# Clock.net
KiCad netlist of a schematic drawn in EAGLE
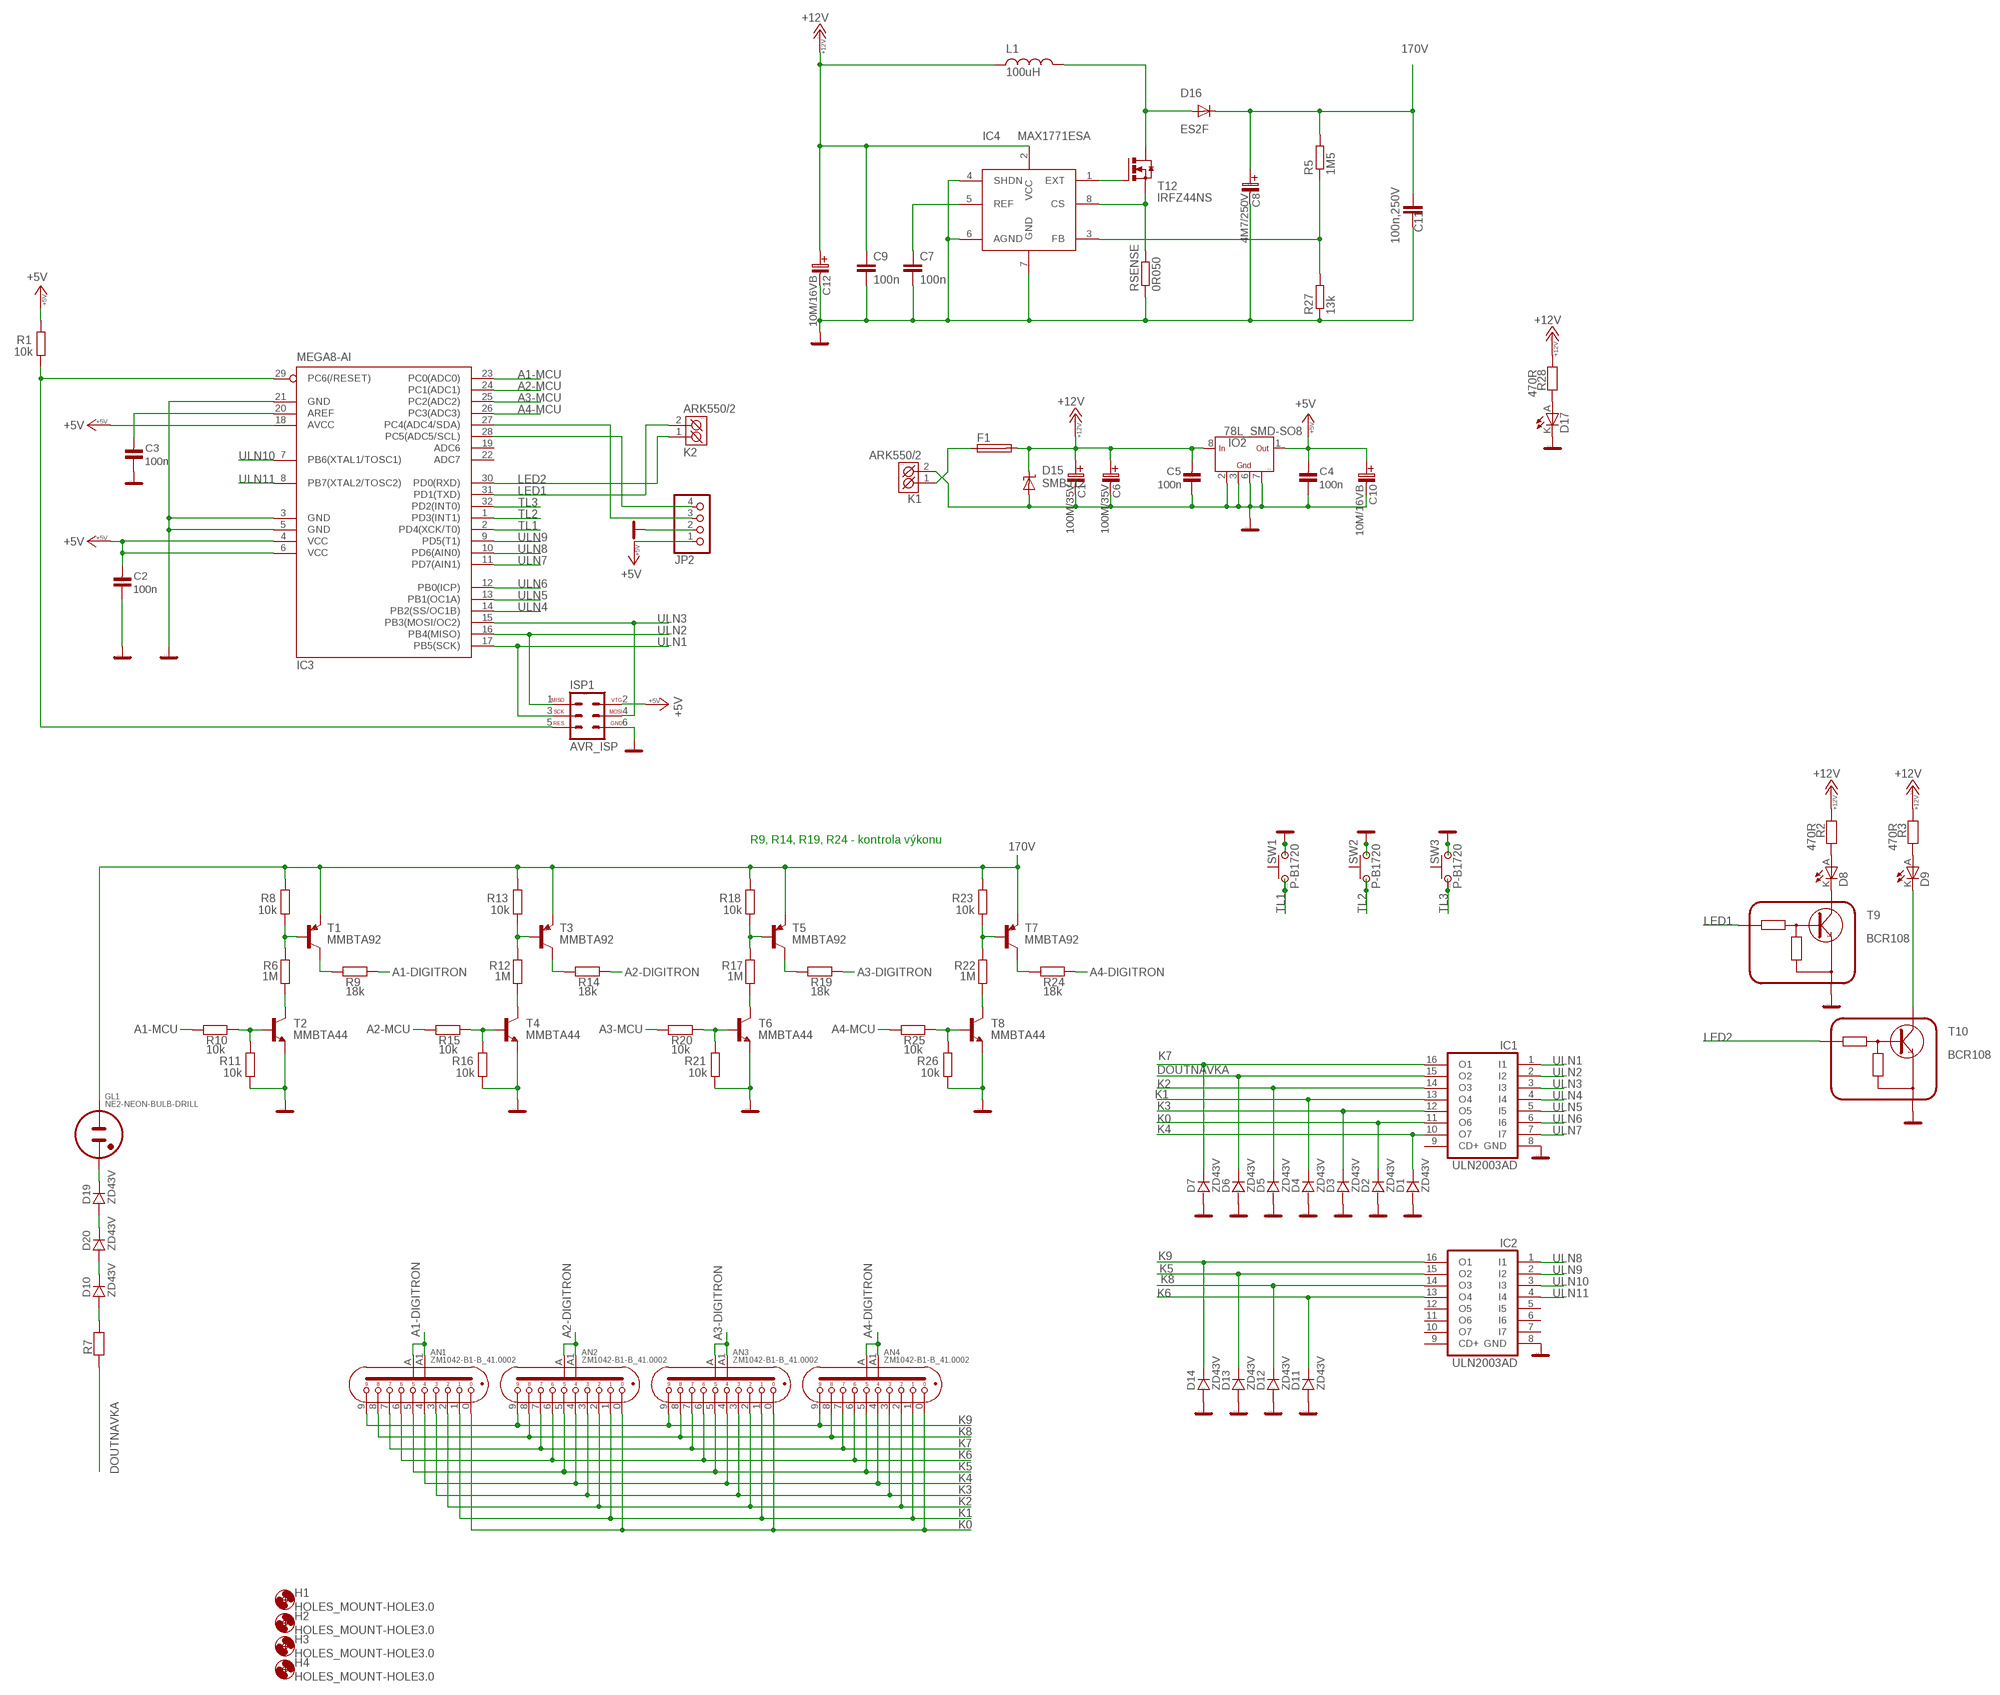
[diagram p0: schematic, sheet 1]

(export (version "E")
  (design (tool "Eeschema 10.0.6"))
  (components
    (comp (ref "AN1")
      (value "ZM1042-B1-B_41.0002")
      (footprint "eagle-import:ZM1042-MULTI-CONTACT")
      (libsource (lib "eagle-import") (part "ZM1042-B1-B_41.0002"))
    )
    (comp (ref "AN2")
      (value "ZM1042-B1-B_41.0002")
      (footprint "eagle-import:ZM1042-MULTI-CONTACT")
      (libsource (lib "eagle-import") (part "ZM1042-B1-B_41.0002"))
    )
    (comp (ref "AN3")
      (value "ZM1042-B1-B_41.0002")
      (footprint "eagle-import:ZM1042-MULTI-CONTACT")
      (libsource (lib "eagle-import") (part "ZM1042-B1-B_41.0002"))
    )
    (comp (ref "AN4")
      (value "ZM1042-B1-B_41.0002")
      (footprint "eagle-import:ZM1042-MULTI-CONTACT")
      (libsource (lib "eagle-import") (part "ZM1042-B1-B_41.0002"))
    )
    (comp (ref "C1")
      (value "100M/35V")
      (footprint "eagle-import:C_EL_3,5")
      (libsource (lib "eagle-import") (part "100M/35V"))
    )
    (comp (ref "C2")
      (value "100n")
      (footprint "eagle-import:0805")
      (libsource (lib "eagle-import") (part "C-KERAMIK_SMD_0805"))
    )
    (comp (ref "C3")
      (value "100n")
      (footprint "eagle-import:0805")
      (libsource (lib "eagle-import") (part "C-KERAMIK_SMD_0805"))
    )
    (comp (ref "C4")
      (value "100n")
      (footprint "eagle-import:0805")
      (libsource (lib "eagle-import") (part "C-KERAMIK_SMD_0805"))
    )
    (comp (ref "C5")
      (value "100n")
      (footprint "eagle-import:0805")
      (libsource (lib "eagle-import") (part "C-KERAMIK_SMD_0805"))
    )
    (comp (ref "C6")
      (value "100M/35V")
      (footprint "eagle-import:C_EL_3,5")
      (libsource (lib "eagle-import") (part "100M/35V"))
    )
    (comp (ref "C7")
      (value "100n")
      (footprint "eagle-import:C0805")
      (libsource (lib "eagle-import") (part "C-EUC0805"))
    )
    (comp (ref "C8")
      (value "4M7/250V")
      (footprint "eagle-import:C_EL_3,5")
      (libsource (lib "eagle-import") (part "4M7/250V"))
    )
    (comp (ref "C9")
      (value "100n")
      (footprint "eagle-import:C0805")
      (libsource (lib "eagle-import") (part "C-EUC0805"))
    )
    (comp (ref "C10")
      (value "10M/16VB")
      (footprint "eagle-import:B")
      (libsource (lib "eagle-import") (part "10M/16VB"))
    )
    (comp (ref "C11")
      (value "100n,250V")
      (footprint "eagle-import:C2420")
      (libsource (lib "eagle-import") (part "C-EU-2420"))
    )
    (comp (ref "C12")
      (value "10M/16VB")
      (footprint "eagle-import:B")
      (libsource (lib "eagle-import") (part "10M/16VB"))
    )
    (comp (ref "D1")
      (value "ZD43V")
      (footprint "eagle-import:SOD-80")
      (libsource (lib "eagle-import") (part "1N4148_SOD80"))
    )
    (comp (ref "D2")
      (value "ZD43V")
      (footprint "eagle-import:SOD-80")
      (libsource (lib "eagle-import") (part "1N4148_SOD80"))
    )
    (comp (ref "D3")
      (value "ZD43V")
      (footprint "eagle-import:SOD-80")
      (libsource (lib "eagle-import") (part "1N4148_SOD80"))
    )
    (comp (ref "D4")
      (value "ZD43V")
      (footprint "eagle-import:SOD-80")
      (libsource (lib "eagle-import") (part "1N4148_SOD80"))
    )
    (comp (ref "D5")
      (value "ZD43V")
      (footprint "eagle-import:SOD-80")
      (libsource (lib "eagle-import") (part "1N4148_SOD80"))
    )
    (comp (ref "D6")
      (value "ZD43V")
      (footprint "eagle-import:SOD-80")
      (libsource (lib "eagle-import") (part "1N4148_SOD80"))
    )
    (comp (ref "D7")
      (value "ZD43V")
      (footprint "eagle-import:SOD-80")
      (libsource (lib "eagle-import") (part "1N4148_SOD80"))
    )
    (comp (ref "D8")
      (value "LEDLED3MM")
      (footprint "eagle-import:LED3MM")
      (libsource (lib "eagle-import") (part "LEDLED3MM"))
    )
    (comp (ref "D9")
      (value "LEDLED3MM")
      (footprint "eagle-import:LED3MM")
      (libsource (lib "eagle-import") (part "LEDLED3MM"))
    )
    (comp (ref "D10")
      (value "ZD43V")
      (footprint "eagle-import:SOD-80")
      (libsource (lib "eagle-import") (part "1N4148_SOD80"))
    )
    (comp (ref "D11")
      (value "ZD43V")
      (footprint "eagle-import:SOD-80")
      (libsource (lib "eagle-import") (part "1N4148_SOD80"))
    )
    (comp (ref "D12")
      (value "ZD43V")
      (footprint "eagle-import:SOD-80")
      (libsource (lib "eagle-import") (part "1N4148_SOD80"))
    )
    (comp (ref "D13")
      (value "ZD43V")
      (footprint "eagle-import:SOD-80")
      (libsource (lib "eagle-import") (part "1N4148_SOD80"))
    )
    (comp (ref "D14")
      (value "ZD43V")
      (footprint "eagle-import:SOD-80")
      (libsource (lib "eagle-import") (part "1N4148_SOD80"))
    )
    (comp (ref "D15")
      (value "SMBJ12")
      (footprint "eagle-import:SMBJ")
      (libsource (lib "eagle-import") (part "SUPPRESSOR-SMBJ"))
    )
    (comp (ref "D16")
      (value "ES2F")
      (footprint "eagle-import:SMC")
      (libsource (lib "eagle-import") (part "DIODE-SMC"))
    )
    (comp (ref "D17")
      (value "LEDLED3MM")
      (footprint "eagle-import:LED3MM")
      (libsource (lib "eagle-import") (part "LEDLED3MM"))
    )
    (comp (ref "D19")
      (value "ZD43V")
      (footprint "eagle-import:SOD-80")
      (libsource (lib "eagle-import") (part "1N4148_SOD80"))
    )
    (comp (ref "D20")
      (value "ZD43V")
      (footprint "eagle-import:SOD-80")
      (libsource (lib "eagle-import") (part "1N4148_SOD80"))
    )
    (comp (ref "F1")
      (value "TE5")
      (footprint "eagle-import:TE5")
      (libsource (lib "eagle-import") (part "TE5"))
    )
    (comp (ref "GL1")
      (value "NE2-NEON-BULB-DRILL")
      (footprint "eagle-import:NE2-NEON-BULB-DRILL")
      (libsource (lib "eagle-import") (part "NE2-NEON-BULB-DRILL"))
    )
    (comp (ref "H1")
      (value "HOLES_MOUNT-HOLE3.0")
      (footprint "eagle-import:HOLES_3,0")
      (libsource (lib "eagle-import") (part "HOLES_MOUNT-HOLE3.0"))
    )
    (comp (ref "H2")
      (value "HOLES_MOUNT-HOLE3.0")
      (footprint "eagle-import:HOLES_3,0")
      (libsource (lib "eagle-import") (part "HOLES_MOUNT-HOLE3.0"))
    )
    (comp (ref "H3")
      (value "HOLES_MOUNT-HOLE3.0")
      (footprint "eagle-import:HOLES_3,0")
      (libsource (lib "eagle-import") (part "HOLES_MOUNT-HOLE3.0"))
    )
    (comp (ref "H4")
      (value "HOLES_MOUNT-HOLE3.0")
      (footprint "eagle-import:HOLES_3,0")
      (libsource (lib "eagle-import") (part "HOLES_MOUNT-HOLE3.0"))
    )
    (comp (ref "IC1")
      (value "ULN2003AD")
      (footprint "eagle-import:SO16")
      (libsource (lib "eagle-import") (part "ULN2003AD"))
    )
    (comp (ref "IC2")
      (value "ULN2003AD")
      (footprint "eagle-import:SO16")
      (libsource (lib "eagle-import") (part "ULN2003AD"))
    )
    (comp (ref "IC3")
      (value "MEGA8-AI")
      (footprint "eagle-import:TQFP32-08")
      (fields (field (name "MPN") "ATMEGA8-16AU"))
      (libsource (lib "eagle-import") (part "MEGA8-AI"))
    )
    (comp (ref "IC4")
      (value "MAX1771ESA")
      (footprint "eagle-import:SO-8")
      (libsource (lib "eagle-import") (part "MAX1771ESA"))
    )
    (comp (ref "IO2")
      (value "78L_SMD-SO8")
      (footprint "eagle-import:SO08")
      (libsource (lib "eagle-import") (part "78L??_SMD-SO8"))
    )
    (comp (ref "ISP1")
      (value "AVR_ISP")
      (footprint "eagle-import:MLW06G")
      (libsource (lib "eagle-import") (part "AVR_ISP"))
    )
    (comp (ref "JP2")
      (value "PINHD-1X4")
      (footprint "eagle-import:1X04")
      (libsource (lib "eagle-import") (part "PINHD-1X4"))
    )
    (comp (ref "K1")
      (value "ARK550/2")
      (footprint "eagle-import:ARK550_2")
      (libsource (lib "eagle-import") (part "ARK550/2"))
    )
    (comp (ref "K2")
      (value "ARK550/2")
      (footprint "eagle-import:ARK550_2")
      (libsource (lib "eagle-import") (part "ARK550/2"))
    )
    (comp (ref "L1")
      (value "100uH")
      (footprint "eagle-import:L-B82479")
      (libsource (lib "eagle-import") (part "L-SMT-POWER-B82479"))
    )
    (comp (ref "R1")
      (value "10k")
      (footprint "eagle-import:0805")
      (libsource (lib "eagle-import") (part "R_SMD_0805"))
    )
    (comp (ref "R2")
      (value "470R")
      (footprint "eagle-import:0805")
      (libsource (lib "eagle-import") (part "#PaJa_30_R_SMD_0805"))
    )
    (comp (ref "R3")
      (value "470R")
      (footprint "eagle-import:0805")
      (libsource (lib "eagle-import") (part "#PaJa_30_R_SMD_0805"))
    )
    (comp (ref "R5")
      (value "1M5")
      (footprint "eagle-import:R0805")
      (libsource (lib "eagle-import") (part "R-EU_R0805"))
    )
    (comp (ref "R6")
      (value "1M")
      (footprint "eagle-import:0805")
      (libsource (lib "eagle-import") (part "R_SMD_0805"))
    )
    (comp (ref "R7")
      (value "W2_180K")
      (footprint "eagle-import:R__2W")
      (libsource (lib "eagle-import") (part "W2_180K"))
    )
    (comp (ref "R8")
      (value "10k")
      (footprint "eagle-import:0805")
      (libsource (lib "eagle-import") (part "R_SMD_0805"))
    )
    (comp (ref "R9")
      (value "18k")
      (footprint "eagle-import:1206")
      (libsource (lib "eagle-import") (part "#PaJa_30_R_SMD_1206"))
    )
    (comp (ref "R10")
      (value "10k")
      (footprint "eagle-import:0805")
      (libsource (lib "eagle-import") (part "#PaJa_30_R_SMD_0805"))
    )
    (comp (ref "R11")
      (value "10k")
      (footprint "eagle-import:0805")
      (libsource (lib "eagle-import") (part "R_SMD_0805"))
    )
    (comp (ref "R12")
      (value "1M")
      (footprint "eagle-import:0805")
      (libsource (lib "eagle-import") (part "R_SMD_0805"))
    )
    (comp (ref "R13")
      (value "10k")
      (footprint "eagle-import:0805")
      (libsource (lib "eagle-import") (part "R_SMD_0805"))
    )
    (comp (ref "R14")
      (value "18k")
      (footprint "eagle-import:1206")
      (libsource (lib "eagle-import") (part "#PaJa_30_R_SMD_1206"))
    )
    (comp (ref "R15")
      (value "10k")
      (footprint "eagle-import:0805")
      (libsource (lib "eagle-import") (part "#PaJa_30_R_SMD_0805"))
    )
    (comp (ref "R16")
      (value "10k")
      (footprint "eagle-import:0805")
      (libsource (lib "eagle-import") (part "R_SMD_0805"))
    )
    (comp (ref "R17")
      (value "1M")
      (footprint "eagle-import:0805")
      (libsource (lib "eagle-import") (part "R_SMD_0805"))
    )
    (comp (ref "R18")
      (value "10k")
      (footprint "eagle-import:0805")
      (libsource (lib "eagle-import") (part "R_SMD_0805"))
    )
    (comp (ref "R19")
      (value "18k")
      (footprint "eagle-import:1206")
      (libsource (lib "eagle-import") (part "#PaJa_30_R_SMD_1206"))
    )
    (comp (ref "R20")
      (value "10k")
      (footprint "eagle-import:0805")
      (libsource (lib "eagle-import") (part "#PaJa_30_R_SMD_0805"))
    )
    (comp (ref "R21")
      (value "10k")
      (footprint "eagle-import:0805")
      (libsource (lib "eagle-import") (part "R_SMD_0805"))
    )
    (comp (ref "R22")
      (value "1M")
      (footprint "eagle-import:0805")
      (libsource (lib "eagle-import") (part "R_SMD_0805"))
    )
    (comp (ref "R23")
      (value "10k")
      (footprint "eagle-import:0805")
      (libsource (lib "eagle-import") (part "R_SMD_0805"))
    )
    (comp (ref "R24")
      (value "18k")
      (footprint "eagle-import:1206")
      (libsource (lib "eagle-import") (part "#PaJa_30_R_SMD_1206"))
    )
    (comp (ref "R25")
      (value "10k")
      (footprint "eagle-import:0805")
      (libsource (lib "eagle-import") (part "#PaJa_30_R_SMD_0805"))
    )
    (comp (ref "R26")
      (value "10k")
      (footprint "eagle-import:0805")
      (libsource (lib "eagle-import") (part "R_SMD_0805"))
    )
    (comp (ref "R27")
      (value "13k")
      (footprint "eagle-import:R0805")
      (libsource (lib "eagle-import") (part "R-EU_R0805"))
    )
    (comp (ref "R28")
      (value "470R")
      (footprint "eagle-import:0805")
      (libsource (lib "eagle-import") (part "#PaJa_30_R_SMD_0805"))
    )
    (comp (ref "RSENSE")
      (value "0R050")
      (footprint "eagle-import:R2010")
      (libsource (lib "eagle-import") (part "R-EU_R2010"))
    )
    (comp (ref "SW1")
      (value "P-B1720")
      (footprint "eagle-import:P-B1720")
      (libsource (lib "eagle-import") (part "P-B1720"))
    )
    (comp (ref "SW2")
      (value "P-B1720")
      (footprint "eagle-import:P-B1720")
      (libsource (lib "eagle-import") (part "P-B1720"))
    )
    (comp (ref "SW3")
      (value "P-B1720")
      (footprint "eagle-import:P-B1720")
      (libsource (lib "eagle-import") (part "P-B1720"))
    )
    (comp (ref "T1")
      (value "MMBTA92")
      (footprint "eagle-import:SOT23-BEC")
      (libsource (lib "eagle-import") (part "-PNP-SOT23-BECMMBTA92LT1"))
    )
    (comp (ref "T2")
      (value "MMBTA44")
      (footprint "eagle-import:SOT23-BEC")
      (libsource (lib "eagle-import") (part "-NPN-SOT23-BECMMBTA42LT1"))
    )
    (comp (ref "T3")
      (value "MMBTA92")
      (footprint "eagle-import:SOT23-BEC")
      (libsource (lib "eagle-import") (part "-PNP-SOT23-BECMMBTA92LT1"))
    )
    (comp (ref "T4")
      (value "MMBTA44")
      (footprint "eagle-import:SOT23-BEC")
      (libsource (lib "eagle-import") (part "-NPN-SOT23-BECMMBTA42LT1"))
    )
    (comp (ref "T5")
      (value "MMBTA92")
      (footprint "eagle-import:SOT23-BEC")
      (libsource (lib "eagle-import") (part "-PNP-SOT23-BECMMBTA92LT1"))
    )
    (comp (ref "T6")
      (value "MMBTA44")
      (footprint "eagle-import:SOT23-BEC")
      (libsource (lib "eagle-import") (part "-NPN-SOT23-BECMMBTA42LT1"))
    )
    (comp (ref "T7")
      (value "MMBTA92")
      (footprint "eagle-import:SOT23-BEC")
      (libsource (lib "eagle-import") (part "-PNP-SOT23-BECMMBTA92LT1"))
    )
    (comp (ref "T8")
      (value "MMBTA44")
      (footprint "eagle-import:SOT23-BEC")
      (libsource (lib "eagle-import") (part "-NPN-SOT23-BECMMBTA42LT1"))
    )
    (comp (ref "T9")
      (value "BCR108")
      (footprint "eagle-import:SOT-23")
      (libsource (lib "eagle-import") (part "BCR108"))
    )
    (comp (ref "T10")
      (value "BCR108")
      (footprint "eagle-import:SOT-23")
      (libsource (lib "eagle-import") (part "BCR108"))
    )
    (comp (ref "T12")
      (value "IRFZ44NS")
      (footprint "eagle-import:D2PACK")
      (libsource (lib "eagle-import") (part "IRF3704S"))
    )
  )
  (nets
    (net (code "1") (name "+5V") (class "Default")
      (node (ref "C10") (pin "+") (pinfunction "C_EL+_+") (pintype "passive"))
      (node (ref "C2") (pin "2") (pinfunction "2_2") (pintype "passive"))
      (node (ref "C4") (pin "2") (pinfunction "2_2") (pintype "passive"))
      (node (ref "IC3") (pin "18") (pinfunction "AVCC_18") (pintype "power_in"))
      (node (ref "IC3") (pin "4") (pinfunction "VCC_4") (pintype "power_in"))
      (node (ref "IC3") (pin "6") (pinfunction "VCC_6") (pintype "power_in"))
      (node (ref "IO2") (pin "1") (pinfunction "OUT_1") (pintype "output"))
      (node (ref "ISP1") (pin "2") (pinfunction "2_2") (pintype "passive"))
      (node (ref "JP2") (pin "1") (pinfunction "1_1") (pintype "passive"))
      (node (ref "R1") (pin "2") (pinfunction "2_2") (pintype "passive"))
    )
    (net (code "2") (name "+12V") (class "Default")
      (node (ref "C1") (pin "C+") (pinfunction "C_EL+_C+") (pintype "passive"))
      (node (ref "C12") (pin "+") (pinfunction "C_EL+_+") (pintype "passive"))
      (node (ref "C5") (pin "2") (pinfunction "2_2") (pintype "passive"))
      (node (ref "C6") (pin "C+") (pinfunction "C_EL+_C+") (pintype "passive"))
      (node (ref "C9") (pin "1") (pinfunction "1_1") (pintype "passive"))
      (node (ref "D15") (pin "C") (pinfunction "C_C") (pintype "passive"))
      (node (ref "F1") (pin "2") (pinfunction "2_2") (pintype "passive"))
      (node (ref "IC4") (pin "2") (pinfunction "VCC_2") (pintype "input"))
      (node (ref "IO2") (pin "8") (pinfunction "IN_8") (pintype "passive"))
      (node (ref "L1") (pin "P$1") (pinfunction "1_P$1") (pintype "passive"))
      (node (ref "R2") (pin "2") (pinfunction "2_2") (pintype "passive"))
      (node (ref "R28") (pin "2") (pinfunction "2_2") (pintype "passive"))
      (node (ref "R3") (pin "2") (pinfunction "2_2") (pintype "passive"))
    )
    (net (code "3") (name "/170V") (class "Default")
      (node (ref "C11") (pin "P$1") (pinfunction "1_P$1") (pintype "passive"))
      (node (ref "C8") (pin "C+") (pinfunction "C_EL+_C+") (pintype "passive"))
      (node (ref "D16") (pin "C") (pinfunction "C_C") (pintype "passive"))
      (node (ref "GL1") (pin "1") (pinfunction "A_1") (pintype "passive"))
      (node (ref "R13") (pin "2") (pinfunction "2_2") (pintype "passive"))
      (node (ref "R18") (pin "2") (pinfunction "2_2") (pintype "passive"))
      (node (ref "R23") (pin "2") (pinfunction "2_2") (pintype "passive"))
      (node (ref "R5") (pin "2") (pinfunction "2_2") (pintype "passive"))
      (node (ref "R8") (pin "2") (pinfunction "2_2") (pintype "passive"))
      (node (ref "T1") (pin "E") (pinfunction "E_E") (pintype "passive"))
      (node (ref "T3") (pin "E") (pinfunction "E_E") (pintype "passive"))
      (node (ref "T5") (pin "E") (pinfunction "E_E") (pintype "passive"))
      (node (ref "T7") (pin "E") (pinfunction "E_E") (pintype "passive"))
    )
    (net (code "4") (name "/A1-DIGITRON") (class "Default")
      (node (ref "AN1") (pin "A") (pinfunction "A1_A") (pintype "passive"))
      (node (ref "AN1") (pin "A1") (pinfunction "A2_A1") (pintype "passive"))
      (node (ref "R9") (pin "1") (pinfunction "1_1") (pintype "passive"))
    )
    (net (code "5") (name "/A1-MCU") (class "Default")
      (node (ref "IC3") (pin "23") (pinfunction "PC0(ADC0)_23") (pintype "bidirectional"))
      (node (ref "R10") (pin "2") (pinfunction "2_2") (pintype "passive"))
    )
    (net (code "6") (name "/A2-DIGITRON") (class "Default")
      (node (ref "AN2") (pin "A") (pinfunction "A1_A") (pintype "passive"))
      (node (ref "AN2") (pin "A1") (pinfunction "A2_A1") (pintype "passive"))
      (node (ref "R14") (pin "1") (pinfunction "1_1") (pintype "passive"))
    )
    (net (code "7") (name "/A2-MCU") (class "Default")
      (node (ref "IC3") (pin "24") (pinfunction "PC1(ADC1)_24") (pintype "bidirectional"))
      (node (ref "R15") (pin "2") (pinfunction "2_2") (pintype "passive"))
    )
    (net (code "8") (name "/A3-DIGITRON") (class "Default")
      (node (ref "AN3") (pin "A") (pinfunction "A1_A") (pintype "passive"))
      (node (ref "AN3") (pin "A1") (pinfunction "A2_A1") (pintype "passive"))
      (node (ref "R19") (pin "1") (pinfunction "1_1") (pintype "passive"))
    )
    (net (code "9") (name "/A3-MCU") (class "Default")
      (node (ref "IC3") (pin "25") (pinfunction "PC2(ADC2)_25") (pintype "bidirectional"))
      (node (ref "R20") (pin "2") (pinfunction "2_2") (pintype "passive"))
    )
    (net (code "10") (name "/A4-DIGITRON") (class "Default")
      (node (ref "AN4") (pin "A") (pinfunction "A1_A") (pintype "passive"))
      (node (ref "AN4") (pin "A1") (pinfunction "A2_A1") (pintype "passive"))
      (node (ref "R24") (pin "1") (pinfunction "1_1") (pintype "passive"))
    )
    (net (code "11") (name "/A4-MCU") (class "Default")
      (node (ref "IC3") (pin "26") (pinfunction "PC3(ADC3)_26") (pintype "bidirectional"))
      (node (ref "R25") (pin "2") (pinfunction "2_2") (pintype "passive"))
    )
    (net (code "12") (name "/DOUTNAVKA") (class "Default")
      (node (ref "D6") (pin "K") (pinfunction "K_K") (pintype "passive"))
      (node (ref "IC1") (pin "15") (pinfunction "O2_15") (pintype "open_collector"))
      (node (ref "R7") (pin "1") (pinfunction "1_1") (pintype "passive"))
    )
    (net (code "13") (name "/K0") (class "Default")
      (node (ref "AN1") (pin "0") (pinfunction "0_0") (pintype "passive"))
      (node (ref "AN2") (pin "0") (pinfunction "0_0") (pintype "passive"))
      (node (ref "AN3") (pin "0") (pinfunction "0_0") (pintype "passive"))
      (node (ref "AN4") (pin "0") (pinfunction "0_0") (pintype "passive"))
      (node (ref "D2") (pin "K") (pinfunction "K_K") (pintype "passive"))
      (node (ref "IC1") (pin "11") (pinfunction "O6_11") (pintype "open_collector"))
    )
    (net (code "14") (name "/K1") (class "Default")
      (node (ref "AN1") (pin "1") (pinfunction "1_1") (pintype "passive"))
      (node (ref "AN2") (pin "1") (pinfunction "1_1") (pintype "passive"))
      (node (ref "AN3") (pin "1") (pinfunction "1_1") (pintype "passive"))
      (node (ref "AN4") (pin "1") (pinfunction "1_1") (pintype "passive"))
      (node (ref "D4") (pin "K") (pinfunction "K_K") (pintype "passive"))
      (node (ref "IC1") (pin "13") (pinfunction "O4_13") (pintype "open_collector"))
    )
    (net (code "15") (name "/K2") (class "Default")
      (node (ref "AN1") (pin "2") (pinfunction "2_2") (pintype "passive"))
      (node (ref "AN2") (pin "2") (pinfunction "2_2") (pintype "passive"))
      (node (ref "AN3") (pin "2") (pinfunction "2_2") (pintype "passive"))
      (node (ref "AN4") (pin "2") (pinfunction "2_2") (pintype "passive"))
      (node (ref "D5") (pin "K") (pinfunction "K_K") (pintype "passive"))
      (node (ref "IC1") (pin "14") (pinfunction "O3_14") (pintype "open_collector"))
    )
    (net (code "16") (name "/K3") (class "Default")
      (node (ref "AN1") (pin "3") (pinfunction "3_3") (pintype "passive"))
      (node (ref "AN2") (pin "3") (pinfunction "3_3") (pintype "passive"))
      (node (ref "AN3") (pin "3") (pinfunction "3_3") (pintype "passive"))
      (node (ref "AN4") (pin "3") (pinfunction "3_3") (pintype "passive"))
      (node (ref "D3") (pin "K") (pinfunction "K_K") (pintype "passive"))
      (node (ref "IC1") (pin "12") (pinfunction "O5_12") (pintype "open_collector"))
    )
    (net (code "17") (name "/K4") (class "Default")
      (node (ref "AN1") (pin "4") (pinfunction "4_4") (pintype "passive"))
      (node (ref "AN2") (pin "4") (pinfunction "4_4") (pintype "passive"))
      (node (ref "AN3") (pin "4") (pinfunction "4_4") (pintype "passive"))
      (node (ref "AN4") (pin "4") (pinfunction "4_4") (pintype "passive"))
      (node (ref "D1") (pin "K") (pinfunction "K_K") (pintype "passive"))
      (node (ref "IC1") (pin "10") (pinfunction "O7_10") (pintype "open_collector"))
    )
    (net (code "18") (name "/K5") (class "Default")
      (node (ref "AN1") (pin "5") (pinfunction "5_5") (pintype "passive"))
      (node (ref "AN2") (pin "5") (pinfunction "5_5") (pintype "passive"))
      (node (ref "AN3") (pin "5") (pinfunction "5_5") (pintype "passive"))
      (node (ref "AN4") (pin "5") (pinfunction "5_5") (pintype "passive"))
      (node (ref "D13") (pin "K") (pinfunction "K_K") (pintype "passive"))
      (node (ref "IC2") (pin "15") (pinfunction "O2_15") (pintype "open_collector"))
    )
    (net (code "19") (name "/K6") (class "Default")
      (node (ref "AN1") (pin "6") (pinfunction "6_6") (pintype "passive"))
      (node (ref "AN2") (pin "6") (pinfunction "6_6") (pintype "passive"))
      (node (ref "AN3") (pin "6") (pinfunction "6_6") (pintype "passive"))
      (node (ref "AN4") (pin "6") (pinfunction "6_6") (pintype "passive"))
      (node (ref "D11") (pin "K") (pinfunction "K_K") (pintype "passive"))
      (node (ref "IC2") (pin "13") (pinfunction "O4_13") (pintype "open_collector"))
    )
    (net (code "20") (name "/K7") (class "Default")
      (node (ref "AN1") (pin "7") (pinfunction "7_7") (pintype "passive"))
      (node (ref "AN2") (pin "7") (pinfunction "7_7") (pintype "passive"))
      (node (ref "AN3") (pin "7") (pinfunction "7_7") (pintype "passive"))
      (node (ref "AN4") (pin "7") (pinfunction "7_7") (pintype "passive"))
      (node (ref "D7") (pin "K") (pinfunction "K_K") (pintype "passive"))
      (node (ref "IC1") (pin "16") (pinfunction "O1_16") (pintype "open_collector"))
    )
    (net (code "21") (name "/K8") (class "Default")
      (node (ref "AN1") (pin "8") (pinfunction "8_8") (pintype "passive"))
      (node (ref "AN2") (pin "8") (pinfunction "8_8") (pintype "passive"))
      (node (ref "AN3") (pin "8") (pinfunction "8_8") (pintype "passive"))
      (node (ref "AN4") (pin "8") (pinfunction "8_8") (pintype "passive"))
      (node (ref "D12") (pin "K") (pinfunction "K_K") (pintype "passive"))
      (node (ref "IC2") (pin "14") (pinfunction "O3_14") (pintype "open_collector"))
    )
    (net (code "22") (name "/K9") (class "Default")
      (node (ref "AN1") (pin "9") (pinfunction "9_9") (pintype "passive"))
      (node (ref "AN2") (pin "9") (pinfunction "9_9") (pintype "passive"))
      (node (ref "AN3") (pin "9") (pinfunction "9_9") (pintype "passive"))
      (node (ref "AN4") (pin "9") (pinfunction "9_9") (pintype "passive"))
      (node (ref "D14") (pin "K") (pinfunction "K_K") (pintype "passive"))
      (node (ref "IC2") (pin "16") (pinfunction "O1_16") (pintype "open_collector"))
    )
    (net (code "23") (name "/LED1") (class "Default")
      (node (ref "IC3") (pin "31") (pinfunction "PD1(TXD)_31") (pintype "bidirectional"))
      (node (ref "K2") (pin "2") (pinfunction "K2_2") (pintype "passive"))
      (node (ref "T9") (pin "1") (pinfunction "B_1") (pintype "passive"))
    )
    (net (code "24") (name "/LED2") (class "Default")
      (node (ref "IC3") (pin "30") (pinfunction "PD0(RXD)_30") (pintype "bidirectional"))
      (node (ref "K2") (pin "1") (pinfunction "K1_1") (pintype "passive"))
      (node (ref "T10") (pin "1") (pinfunction "B_1") (pintype "passive"))
    )
    (net (code "25") (name "/TL1") (class "Default")
      (node (ref "IC3") (pin "2") (pinfunction "PD4(XCK/T0)_2") (pintype "bidirectional"))
      (node (ref "SW1") (pin "1") (pinfunction "1_1") (pintype "passive"))
      (node (ref "SW1") (pin "3") (pinfunction "3_3") (pintype "passive"))
    )
    (net (code "26") (name "/TL2") (class "Default")
      (node (ref "IC3") (pin "1") (pinfunction "PD3(INT1)_1") (pintype "bidirectional"))
      (node (ref "SW2") (pin "1") (pinfunction "1_1") (pintype "passive"))
      (node (ref "SW2") (pin "3") (pinfunction "3_3") (pintype "passive"))
    )
    (net (code "27") (name "/TL3") (class "Default")
      (node (ref "IC3") (pin "32") (pinfunction "PD2(INT0)_32") (pintype "bidirectional"))
      (node (ref "SW3") (pin "1") (pinfunction "1_1") (pintype "passive"))
      (node (ref "SW3") (pin "3") (pinfunction "3_3") (pintype "passive"))
    )
    (net (code "28") (name "/ULN1") (class "Default")
      (node (ref "IC1") (pin "1") (pinfunction "I1_1") (pintype "input"))
      (node (ref "IC3") (pin "17") (pinfunction "PB5(SCK)_17") (pintype "bidirectional"))
      (node (ref "ISP1") (pin "3") (pinfunction "3_3") (pintype "passive"))
    )
    (net (code "29") (name "/ULN2") (class "Default")
      (node (ref "IC1") (pin "2") (pinfunction "I2_2") (pintype "input"))
      (node (ref "IC3") (pin "16") (pinfunction "PB4(MISO)_16") (pintype "bidirectional"))
      (node (ref "ISP1") (pin "1") (pinfunction "1_1") (pintype "passive"))
    )
    (net (code "30") (name "/ULN3") (class "Default")
      (node (ref "IC1") (pin "3") (pinfunction "I3_3") (pintype "input"))
      (node (ref "IC3") (pin "15") (pinfunction "PB3(MOSI/OC2)_15") (pintype "bidirectional"))
      (node (ref "ISP1") (pin "4") (pinfunction "4_4") (pintype "passive"))
    )
    (net (code "31") (name "/ULN4") (class "Default")
      (node (ref "IC1") (pin "4") (pinfunction "I4_4") (pintype "input"))
      (node (ref "IC3") (pin "14") (pinfunction "PB2(SS/OC1B)_14") (pintype "bidirectional"))
    )
    (net (code "32") (name "/ULN5") (class "Default")
      (node (ref "IC1") (pin "5") (pinfunction "I5_5") (pintype "input"))
      (node (ref "IC3") (pin "13") (pinfunction "PB1(OC1A)_13") (pintype "bidirectional"))
    )
    (net (code "33") (name "/ULN6") (class "Default")
      (node (ref "IC1") (pin "6") (pinfunction "I6_6") (pintype "input"))
      (node (ref "IC3") (pin "12") (pinfunction "PB0(ICP)_12") (pintype "bidirectional"))
    )
    (net (code "34") (name "/ULN7") (class "Default")
      (node (ref "IC1") (pin "7") (pinfunction "I7_7") (pintype "input"))
      (node (ref "IC3") (pin "11") (pinfunction "PD7(AIN1)_11") (pintype "bidirectional"))
    )
    (net (code "35") (name "/ULN8") (class "Default")
      (node (ref "IC2") (pin "1") (pinfunction "I1_1") (pintype "input"))
      (node (ref "IC3") (pin "10") (pinfunction "PD6(AIN0)_10") (pintype "bidirectional"))
    )
    (net (code "36") (name "/ULN9") (class "Default")
      (node (ref "IC2") (pin "2") (pinfunction "I2_2") (pintype "input"))
      (node (ref "IC3") (pin "9") (pinfunction "PD5(T1)_9") (pintype "bidirectional"))
    )
    (net (code "37") (name "/ULN10") (class "Default")
      (node (ref "IC2") (pin "3") (pinfunction "I3_3") (pintype "input"))
      (node (ref "IC3") (pin "7") (pinfunction "PB6(XTAL1/TOSC1)_7") (pintype "bidirectional"))
    )
    (net (code "38") (name "/ULN11") (class "Default")
      (node (ref "IC2") (pin "4") (pinfunction "I4_4") (pintype "input"))
      (node (ref "IC3") (pin "8") (pinfunction "PB7(XTAL2/TOSC2)_8") (pintype "bidirectional"))
    )
    (net (code "39") (name "GND") (class "Default")
      (node (ref "C1") (pin "C-") (pinfunction "C_EL-_C-") (pintype "passive"))
      (node (ref "C10") (pin "-") (pinfunction "C_EL-_-") (pintype "passive"))
      (node (ref "C11") (pin "P$2") (pinfunction "2_P$2") (pintype "passive"))
      (node (ref "C12") (pin "-") (pinfunction "C_EL-_-") (pintype "passive"))
      (node (ref "C2") (pin "1") (pinfunction "1_1") (pintype "passive"))
      (node (ref "C3") (pin "1") (pinfunction "1_1") (pintype "passive"))
      (node (ref "C4") (pin "1") (pinfunction "1_1") (pintype "passive"))
      (node (ref "C5") (pin "1") (pinfunction "1_1") (pintype "passive"))
      (node (ref "C6") (pin "C-") (pinfunction "C_EL-_C-") (pintype "passive"))
      (node (ref "C7") (pin "2") (pinfunction "2_2") (pintype "passive"))
      (node (ref "C8") (pin "C-") (pinfunction "C_EL-_C-") (pintype "passive"))
      (node (ref "C9") (pin "2") (pinfunction "2_2") (pintype "passive"))
      (node (ref "D1") (pin "A") (pinfunction "A_A") (pintype "passive"))
      (node (ref "D11") (pin "A") (pinfunction "A_A") (pintype "passive"))
      (node (ref "D12") (pin "A") (pinfunction "A_A") (pintype "passive"))
      (node (ref "D13") (pin "A") (pinfunction "A_A") (pintype "passive"))
      (node (ref "D14") (pin "A") (pinfunction "A_A") (pintype "passive"))
      (node (ref "D15") (pin "A") (pinfunction "A_A") (pintype "passive"))
      (node (ref "D17") (pin "K") (pinfunction "C_K") (pintype "passive"))
      (node (ref "D2") (pin "A") (pinfunction "A_A") (pintype "passive"))
      (node (ref "D3") (pin "A") (pinfunction "A_A") (pintype "passive"))
      (node (ref "D4") (pin "A") (pinfunction "A_A") (pintype "passive"))
      (node (ref "D5") (pin "A") (pinfunction "A_A") (pintype "passive"))
      (node (ref "D6") (pin "A") (pinfunction "A_A") (pintype "passive"))
      (node (ref "D7") (pin "A") (pinfunction "A_A") (pintype "passive"))
      (node (ref "IC1") (pin "8") (pinfunction "GND_8") (pintype "power_in"))
      (node (ref "IC2") (pin "8") (pinfunction "GND_8") (pintype "power_in"))
      (node (ref "IC3") (pin "21") (pinfunction "GND_21") (pintype "power_in"))
      (node (ref "IC3") (pin "3") (pinfunction "GND_3") (pintype "power_in"))
      (node (ref "IC3") (pin "5") (pinfunction "GND_5") (pintype "power_in"))
      (node (ref "IC4") (pin "4") (pinfunction "SHDN_4") (pintype "input"))
      (node (ref "IC4") (pin "6") (pinfunction "AGND_6") (pintype "input"))
      (node (ref "IC4") (pin "7") (pinfunction "GND_7") (pintype "input"))
      (node (ref "IO2") (pin "2") (pinfunction "GND_2") (pintype "power_in"))
      (node (ref "IO2") (pin "3") (pinfunction "GND_3") (pintype "power_in"))
      (node (ref "IO2") (pin "6") (pinfunction "GND_6") (pintype "power_in"))
      (node (ref "IO2") (pin "7") (pinfunction "GND_7") (pintype "power_in"))
      (node (ref "ISP1") (pin "6") (pinfunction "6_6") (pintype "passive"))
      (node (ref "JP2") (pin "2") (pinfunction "2_2") (pintype "passive"))
      (node (ref "K1") (pin "2") (pinfunction "K2_2") (pintype "passive"))
      (node (ref "R11") (pin "1") (pinfunction "1_1") (pintype "passive"))
      (node (ref "R16") (pin "1") (pinfunction "1_1") (pintype "passive"))
      (node (ref "R21") (pin "1") (pinfunction "1_1") (pintype "passive"))
      (node (ref "R26") (pin "1") (pinfunction "1_1") (pintype "passive"))
      (node (ref "R27") (pin "1") (pinfunction "1_1") (pintype "passive"))
      (node (ref "RSENSE") (pin "1") (pinfunction "1_1") (pintype "passive"))
      (node (ref "SW1") (pin "2") (pinfunction "2_2") (pintype "passive"))
      (node (ref "SW1") (pin "4") (pinfunction "4_4") (pintype "passive"))
      (node (ref "SW2") (pin "2") (pinfunction "2_2") (pintype "passive"))
      (node (ref "SW2") (pin "4") (pinfunction "4_4") (pintype "passive"))
      (node (ref "SW3") (pin "2") (pinfunction "2_2") (pintype "passive"))
      (node (ref "SW3") (pin "4") (pinfunction "4_4") (pintype "passive"))
      (node (ref "T10") (pin "2") (pinfunction "E_2") (pintype "passive"))
      (node (ref "T2") (pin "E") (pinfunction "E_E") (pintype "passive"))
      (node (ref "T4") (pin "E") (pinfunction "E_E") (pintype "passive"))
      (node (ref "T6") (pin "E") (pinfunction "E_E") (pintype "passive"))
      (node (ref "T8") (pin "E") (pinfunction "E_E") (pintype "passive"))
      (node (ref "T9") (pin "2") (pinfunction "E_2") (pintype "passive"))
    )
    (net (code "40") (name "Net-(D8-C)") (class "Default")
      (node (ref "D8") (pin "K") (pinfunction "C_K") (pintype "passive"))
      (node (ref "T9") (pin "3") (pinfunction "C_3") (pintype "passive"))
    )
    (net (code "41") (name "Net-(D8-PadA)") (class "Default")
      (node (ref "D8") (pin "A") (pinfunction "A_A") (pintype "passive"))
      (node (ref "R2") (pin "1") (pinfunction "1_1") (pintype "passive"))
    )
    (net (code "42") (name "Net-(D9-C)") (class "Default")
      (node (ref "D9") (pin "K") (pinfunction "C_K") (pintype "passive"))
      (node (ref "T10") (pin "3") (pinfunction "C_3") (pintype "passive"))
    )
    (net (code "43") (name "Net-(D9-PadA)") (class "Default")
      (node (ref "D9") (pin "A") (pinfunction "A_A") (pintype "passive"))
      (node (ref "R3") (pin "1") (pinfunction "1_1") (pintype "passive"))
    )
    (net (code "44") (name "Net-(D10-PadA)") (class "Default")
      (node (ref "D10") (pin "A") (pinfunction "A_A") (pintype "passive"))
      (node (ref "R7") (pin "2") (pinfunction "2_2") (pintype "passive"))
    )
    (net (code "45") (name "Net-(D10-PadK)") (class "Default")
      (node (ref "D10") (pin "K") (pinfunction "K_K") (pintype "passive"))
      (node (ref "D20") (pin "A") (pinfunction "A_A") (pintype "passive"))
    )
    (net (code "46") (name "Net-(D17-PadA)") (class "Default")
      (node (ref "D17") (pin "A") (pinfunction "A_A") (pintype "passive"))
      (node (ref "R28") (pin "1") (pinfunction "1_1") (pintype "passive"))
    )
    (net (code "47") (name "Net-(D19-PadA)") (class "Default")
      (node (ref "D19") (pin "A") (pinfunction "A_A") (pintype "passive"))
      (node (ref "D20") (pin "K") (pinfunction "K_K") (pintype "passive"))
    )
    (net (code "48") (name "Net-(GL1-A1)") (class "Default")
      (node (ref "D19") (pin "K") (pinfunction "K_K") (pintype "passive"))
      (node (ref "GL1") (pin "2") (pinfunction "A1_2") (pintype "passive"))
    )
    (net (code "49") (name "Net-(IC3-AREF)") (class "Default")
      (node (ref "C3") (pin "2") (pinfunction "2_2") (pintype "passive"))
      (node (ref "IC3") (pin "20") (pinfunction "AREF_20") (pintype "passive"))
    )
    (net (code "50") (name "Net-(IC3-PC4(ADC4{slash}SDA))") (class "Default")
      (node (ref "IC3") (pin "27") (pinfunction "PC4(ADC4/SDA)_27") (pintype "bidirectional"))
      (node (ref "JP2") (pin "3") (pinfunction "3_3") (pintype "passive"))
    )
    (net (code "51") (name "Net-(IC3-PC5(ADC5{slash}SCL))") (class "Default")
      (node (ref "IC3") (pin "28") (pinfunction "PC5(ADC5/SCL)_28") (pintype "bidirectional"))
      (node (ref "JP2") (pin "4") (pinfunction "4_4") (pintype "passive"))
    )
    (net (code "52") (name "Net-(IC3-PC6({slash}RESET))") (class "Default")
      (node (ref "IC3") (pin "29") (pinfunction "PC6(/RESET)_29") (pintype "bidirectional"))
      (node (ref "ISP1") (pin "5") (pinfunction "5_5") (pintype "passive"))
      (node (ref "R1") (pin "1") (pinfunction "1_1") (pintype "passive"))
    )
    (net (code "53") (name "Net-(IC4-CS)") (class "Default")
      (node (ref "IC4") (pin "8") (pinfunction "CS_8") (pintype "input"))
      (node (ref "RSENSE") (pin "2") (pinfunction "2_2") (pintype "passive"))
      (node (ref "T12") (pin "3") (pinfunction "S_3") (pintype "passive"))
    )
    (net (code "54") (name "Net-(IC4-EXT)") (class "Default")
      (node (ref "IC4") (pin "1") (pinfunction "EXT_1") (pintype "output"))
      (node (ref "T12") (pin "1") (pinfunction "G_1") (pintype "passive"))
    )
    (net (code "55") (name "Net-(IC4-FB)") (class "Default")
      (node (ref "IC4") (pin "3") (pinfunction "FB_3") (pintype "input"))
      (node (ref "R27") (pin "2") (pinfunction "2_2") (pintype "passive"))
      (node (ref "R5") (pin "1") (pinfunction "1_1") (pintype "passive"))
    )
    (net (code "56") (name "Net-(IC4-REF)") (class "Default")
      (node (ref "C7") (pin "1") (pinfunction "1_1") (pintype "passive"))
      (node (ref "IC4") (pin "5") (pinfunction "REF_5") (pintype "input"))
    )
    (net (code "57") (name "Net-(K1-K1)") (class "Default")
      (node (ref "F1") (pin "1") (pinfunction "1_1") (pintype "passive"))
      (node (ref "K1") (pin "1") (pinfunction "K1_1") (pintype "passive"))
    )
    (net (code "58") (name "Net-(L1-2)") (class "Default")
      (node (ref "D16") (pin "A") (pinfunction "A_A") (pintype "passive"))
      (node (ref "L1") (pin "P$2") (pinfunction "2_P$2") (pintype "passive"))
      (node (ref "T12") (pin "2") (pinfunction "D_2") (pintype "passive"))
    )
    (net (code "59") (name "Net-(R6-Pad1)") (class "Default")
      (node (ref "R6") (pin "1") (pinfunction "1_1") (pintype "passive"))
      (node (ref "T2") (pin "C") (pinfunction "C_C") (pintype "passive"))
    )
    (net (code "60") (name "Net-(R6-Pad2)") (class "Default")
      (node (ref "R6") (pin "2") (pinfunction "2_2") (pintype "passive"))
      (node (ref "R8") (pin "1") (pinfunction "1_1") (pintype "passive"))
      (node (ref "T1") (pin "B") (pinfunction "B_B") (pintype "passive"))
    )
    (net (code "61") (name "Net-(R9-Pad2)") (class "Default")
      (node (ref "R9") (pin "2") (pinfunction "2_2") (pintype "passive"))
      (node (ref "T1") (pin "C") (pinfunction "C_C") (pintype "passive"))
    )
    (net (code "62") (name "Net-(R10-Pad1)") (class "Default")
      (node (ref "R10") (pin "1") (pinfunction "1_1") (pintype "passive"))
      (node (ref "R11") (pin "2") (pinfunction "2_2") (pintype "passive"))
      (node (ref "T2") (pin "B") (pinfunction "B_B") (pintype "passive"))
    )
    (net (code "63") (name "Net-(R12-Pad1)") (class "Default")
      (node (ref "R12") (pin "1") (pinfunction "1_1") (pintype "passive"))
      (node (ref "T4") (pin "C") (pinfunction "C_C") (pintype "passive"))
    )
    (net (code "64") (name "Net-(R12-Pad2)") (class "Default")
      (node (ref "R12") (pin "2") (pinfunction "2_2") (pintype "passive"))
      (node (ref "R13") (pin "1") (pinfunction "1_1") (pintype "passive"))
      (node (ref "T3") (pin "B") (pinfunction "B_B") (pintype "passive"))
    )
    (net (code "65") (name "Net-(R14-Pad2)") (class "Default")
      (node (ref "R14") (pin "2") (pinfunction "2_2") (pintype "passive"))
      (node (ref "T3") (pin "C") (pinfunction "C_C") (pintype "passive"))
    )
    (net (code "66") (name "Net-(R15-Pad1)") (class "Default")
      (node (ref "R15") (pin "1") (pinfunction "1_1") (pintype "passive"))
      (node (ref "R16") (pin "2") (pinfunction "2_2") (pintype "passive"))
      (node (ref "T4") (pin "B") (pinfunction "B_B") (pintype "passive"))
    )
    (net (code "67") (name "Net-(R17-Pad1)") (class "Default")
      (node (ref "R17") (pin "1") (pinfunction "1_1") (pintype "passive"))
      (node (ref "T6") (pin "C") (pinfunction "C_C") (pintype "passive"))
    )
    (net (code "68") (name "Net-(R17-Pad2)") (class "Default")
      (node (ref "R17") (pin "2") (pinfunction "2_2") (pintype "passive"))
      (node (ref "R18") (pin "1") (pinfunction "1_1") (pintype "passive"))
      (node (ref "T5") (pin "B") (pinfunction "B_B") (pintype "passive"))
    )
    (net (code "69") (name "Net-(R19-Pad2)") (class "Default")
      (node (ref "R19") (pin "2") (pinfunction "2_2") (pintype "passive"))
      (node (ref "T5") (pin "C") (pinfunction "C_C") (pintype "passive"))
    )
    (net (code "70") (name "Net-(R20-Pad1)") (class "Default")
      (node (ref "R20") (pin "1") (pinfunction "1_1") (pintype "passive"))
      (node (ref "R21") (pin "2") (pinfunction "2_2") (pintype "passive"))
      (node (ref "T6") (pin "B") (pinfunction "B_B") (pintype "passive"))
    )
    (net (code "71") (name "Net-(R22-Pad1)") (class "Default")
      (node (ref "R22") (pin "1") (pinfunction "1_1") (pintype "passive"))
      (node (ref "T8") (pin "C") (pinfunction "C_C") (pintype "passive"))
    )
    (net (code "72") (name "Net-(R22-Pad2)") (class "Default")
      (node (ref "R22") (pin "2") (pinfunction "2_2") (pintype "passive"))
      (node (ref "R23") (pin "1") (pinfunction "1_1") (pintype "passive"))
      (node (ref "T7") (pin "B") (pinfunction "B_B") (pintype "passive"))
    )
    (net (code "73") (name "Net-(R24-Pad2)") (class "Default")
      (node (ref "R24") (pin "2") (pinfunction "2_2") (pintype "passive"))
      (node (ref "T7") (pin "C") (pinfunction "C_C") (pintype "passive"))
    )
    (net (code "74") (name "Net-(R25-Pad1)") (class "Default")
      (node (ref "R25") (pin "1") (pinfunction "1_1") (pintype "passive"))
      (node (ref "R26") (pin "2") (pinfunction "2_2") (pintype "passive"))
      (node (ref "T8") (pin "B") (pinfunction "B_B") (pintype "passive"))
    )
    (net (code "75") (name "unconnected-(IC1-CD+-Pad9)") (class "Default")
      (node (ref "IC1") (pin "9") (pinfunction "CD+_9") (pintype "passive"))
    )
    (net (code "76") (name "unconnected-(IC2-CD+-Pad9)") (class "Default")
      (node (ref "IC2") (pin "9") (pinfunction "CD+_9") (pintype "passive"))
    )
    (net (code "77") (name "unconnected-(IC2-I5-Pad5)") (class "Default")
      (node (ref "IC2") (pin "5") (pinfunction "I5_5") (pintype "input"))
    )
    (net (code "78") (name "unconnected-(IC2-I6-Pad6)") (class "Default")
      (node (ref "IC2") (pin "6") (pinfunction "I6_6") (pintype "input"))
    )
    (net (code "79") (name "unconnected-(IC2-I7-Pad7)") (class "Default")
      (node (ref "IC2") (pin "7") (pinfunction "I7_7") (pintype "input"))
    )
    (net (code "80") (name "unconnected-(IC2-O5-Pad12)") (class "Default")
      (node (ref "IC2") (pin "12") (pinfunction "O5_12") (pintype "open_collector"))
    )
    (net (code "81") (name "unconnected-(IC2-O6-Pad11)") (class "Default")
      (node (ref "IC2") (pin "11") (pinfunction "O6_11") (pintype "open_collector"))
    )
    (net (code "82") (name "unconnected-(IC2-O7-Pad10)") (class "Default")
      (node (ref "IC2") (pin "10") (pinfunction "O7_10") (pintype "open_collector"))
    )
    (net (code "83") (name "unconnected-(IC3-ADC6-Pad19)") (class "Default")
      (node (ref "IC3") (pin "19") (pinfunction "ADC6_19") (pintype "bidirectional"))
    )
    (net (code "84") (name "unconnected-(IC3-ADC7-Pad22)") (class "Default")
      (node (ref "IC3") (pin "22") (pinfunction "ADC7_22") (pintype "bidirectional"))
    )
  )
)
